# IR_Interface_Board.net
KiCad netlist of a schematic drawn in EAGLE
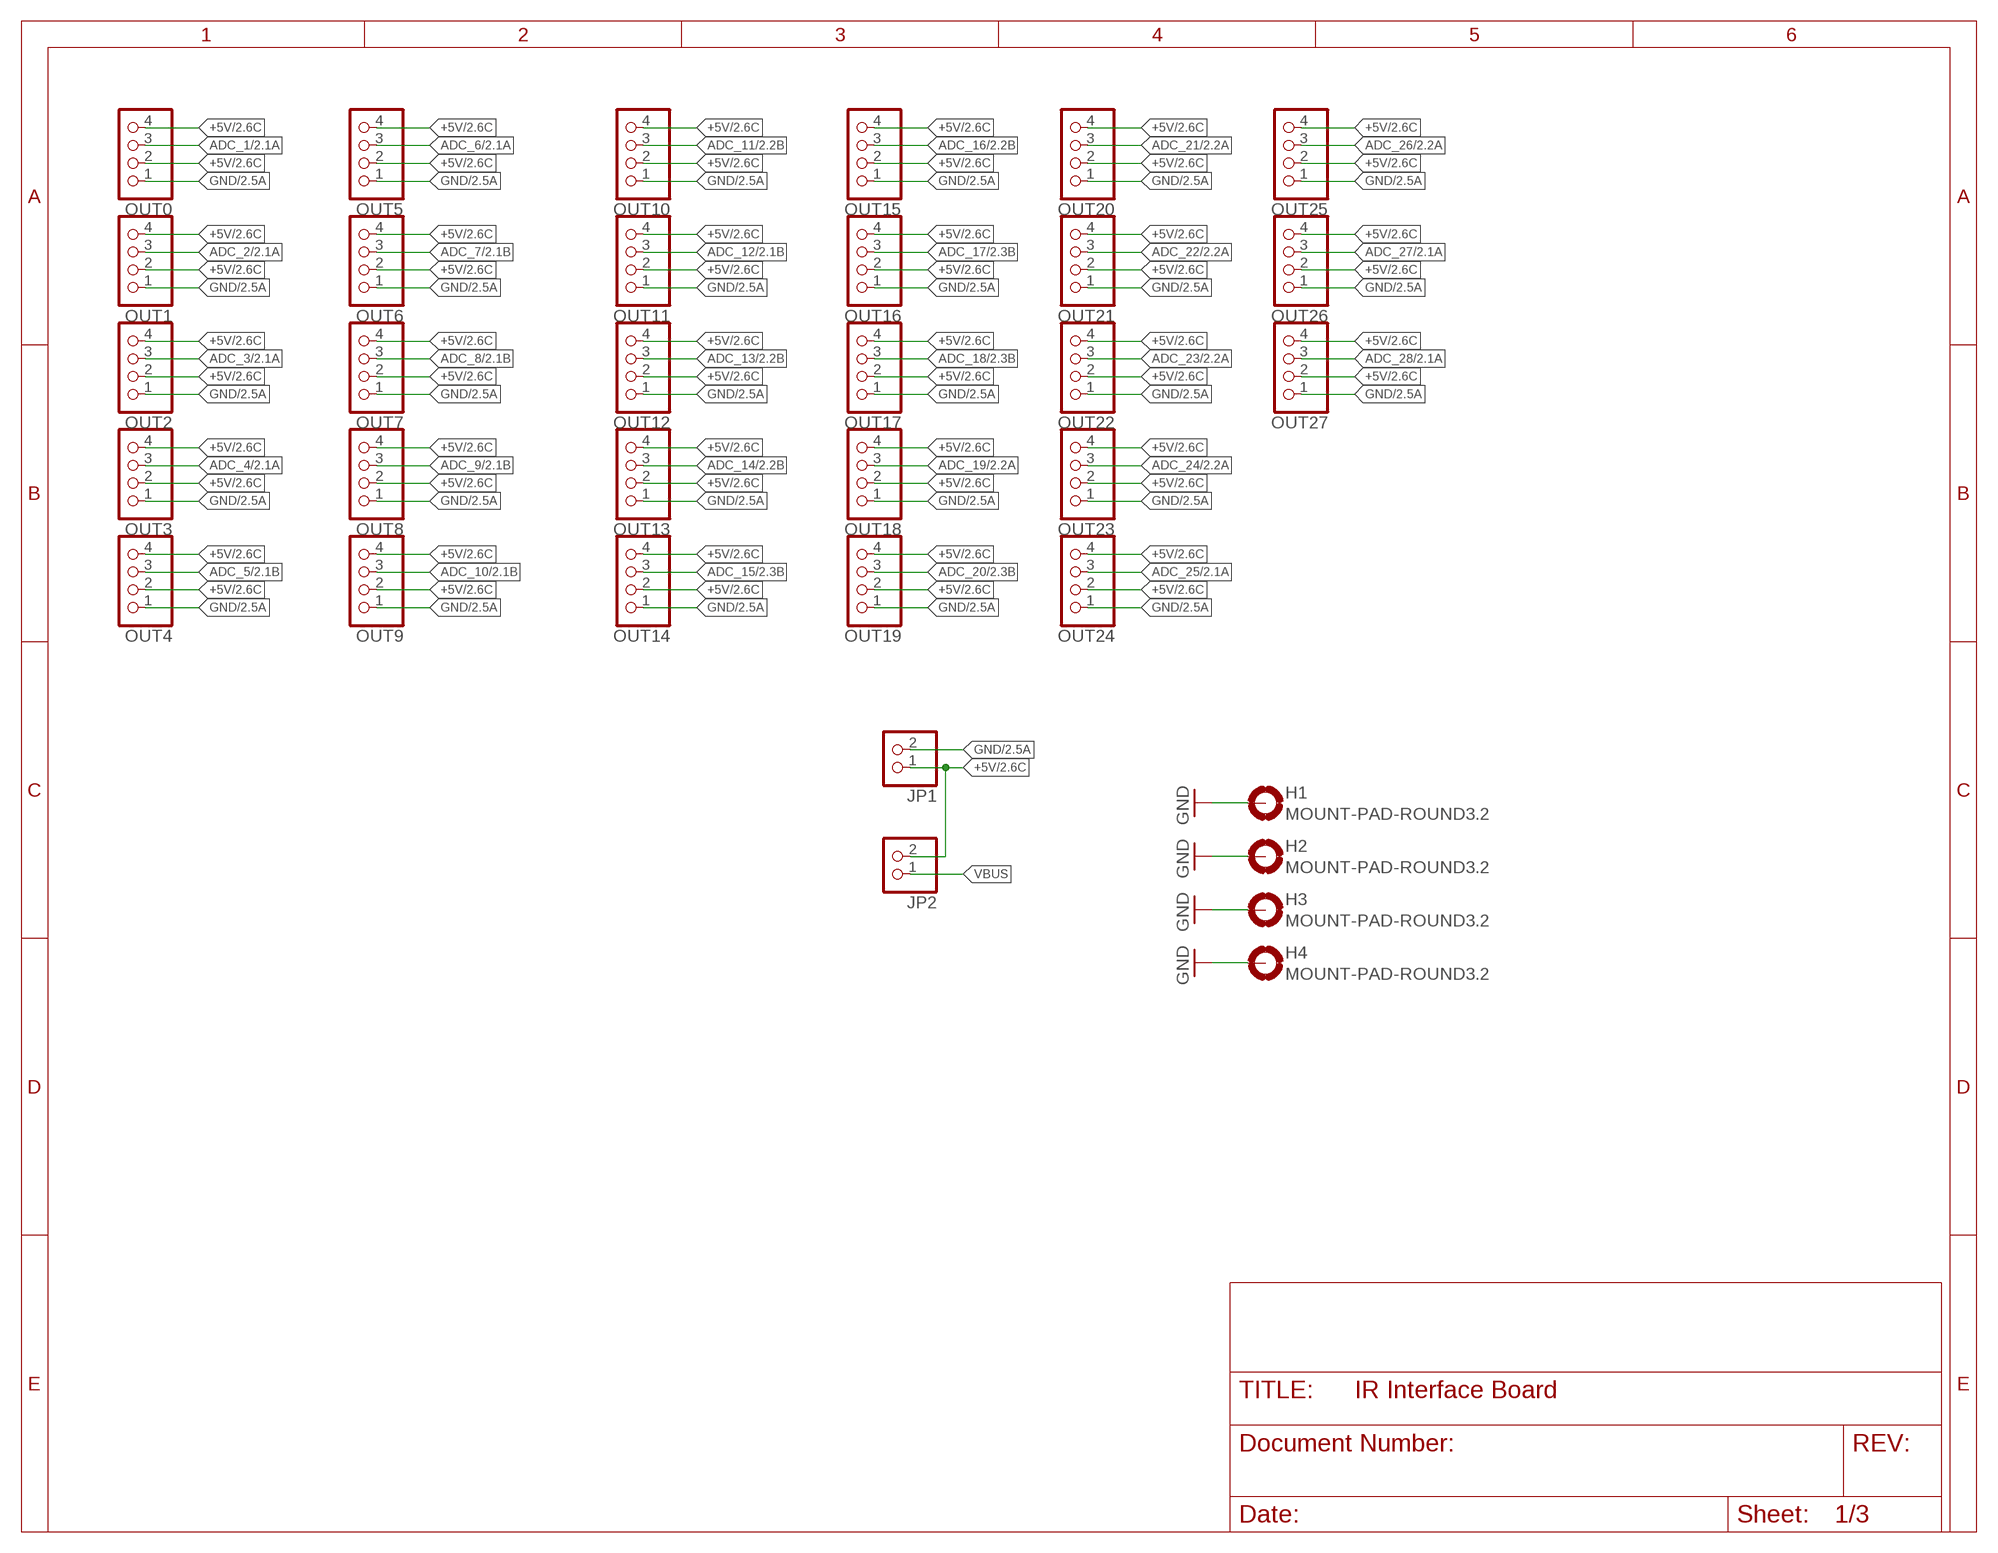
[diagram p0: schematic, sheet 1]
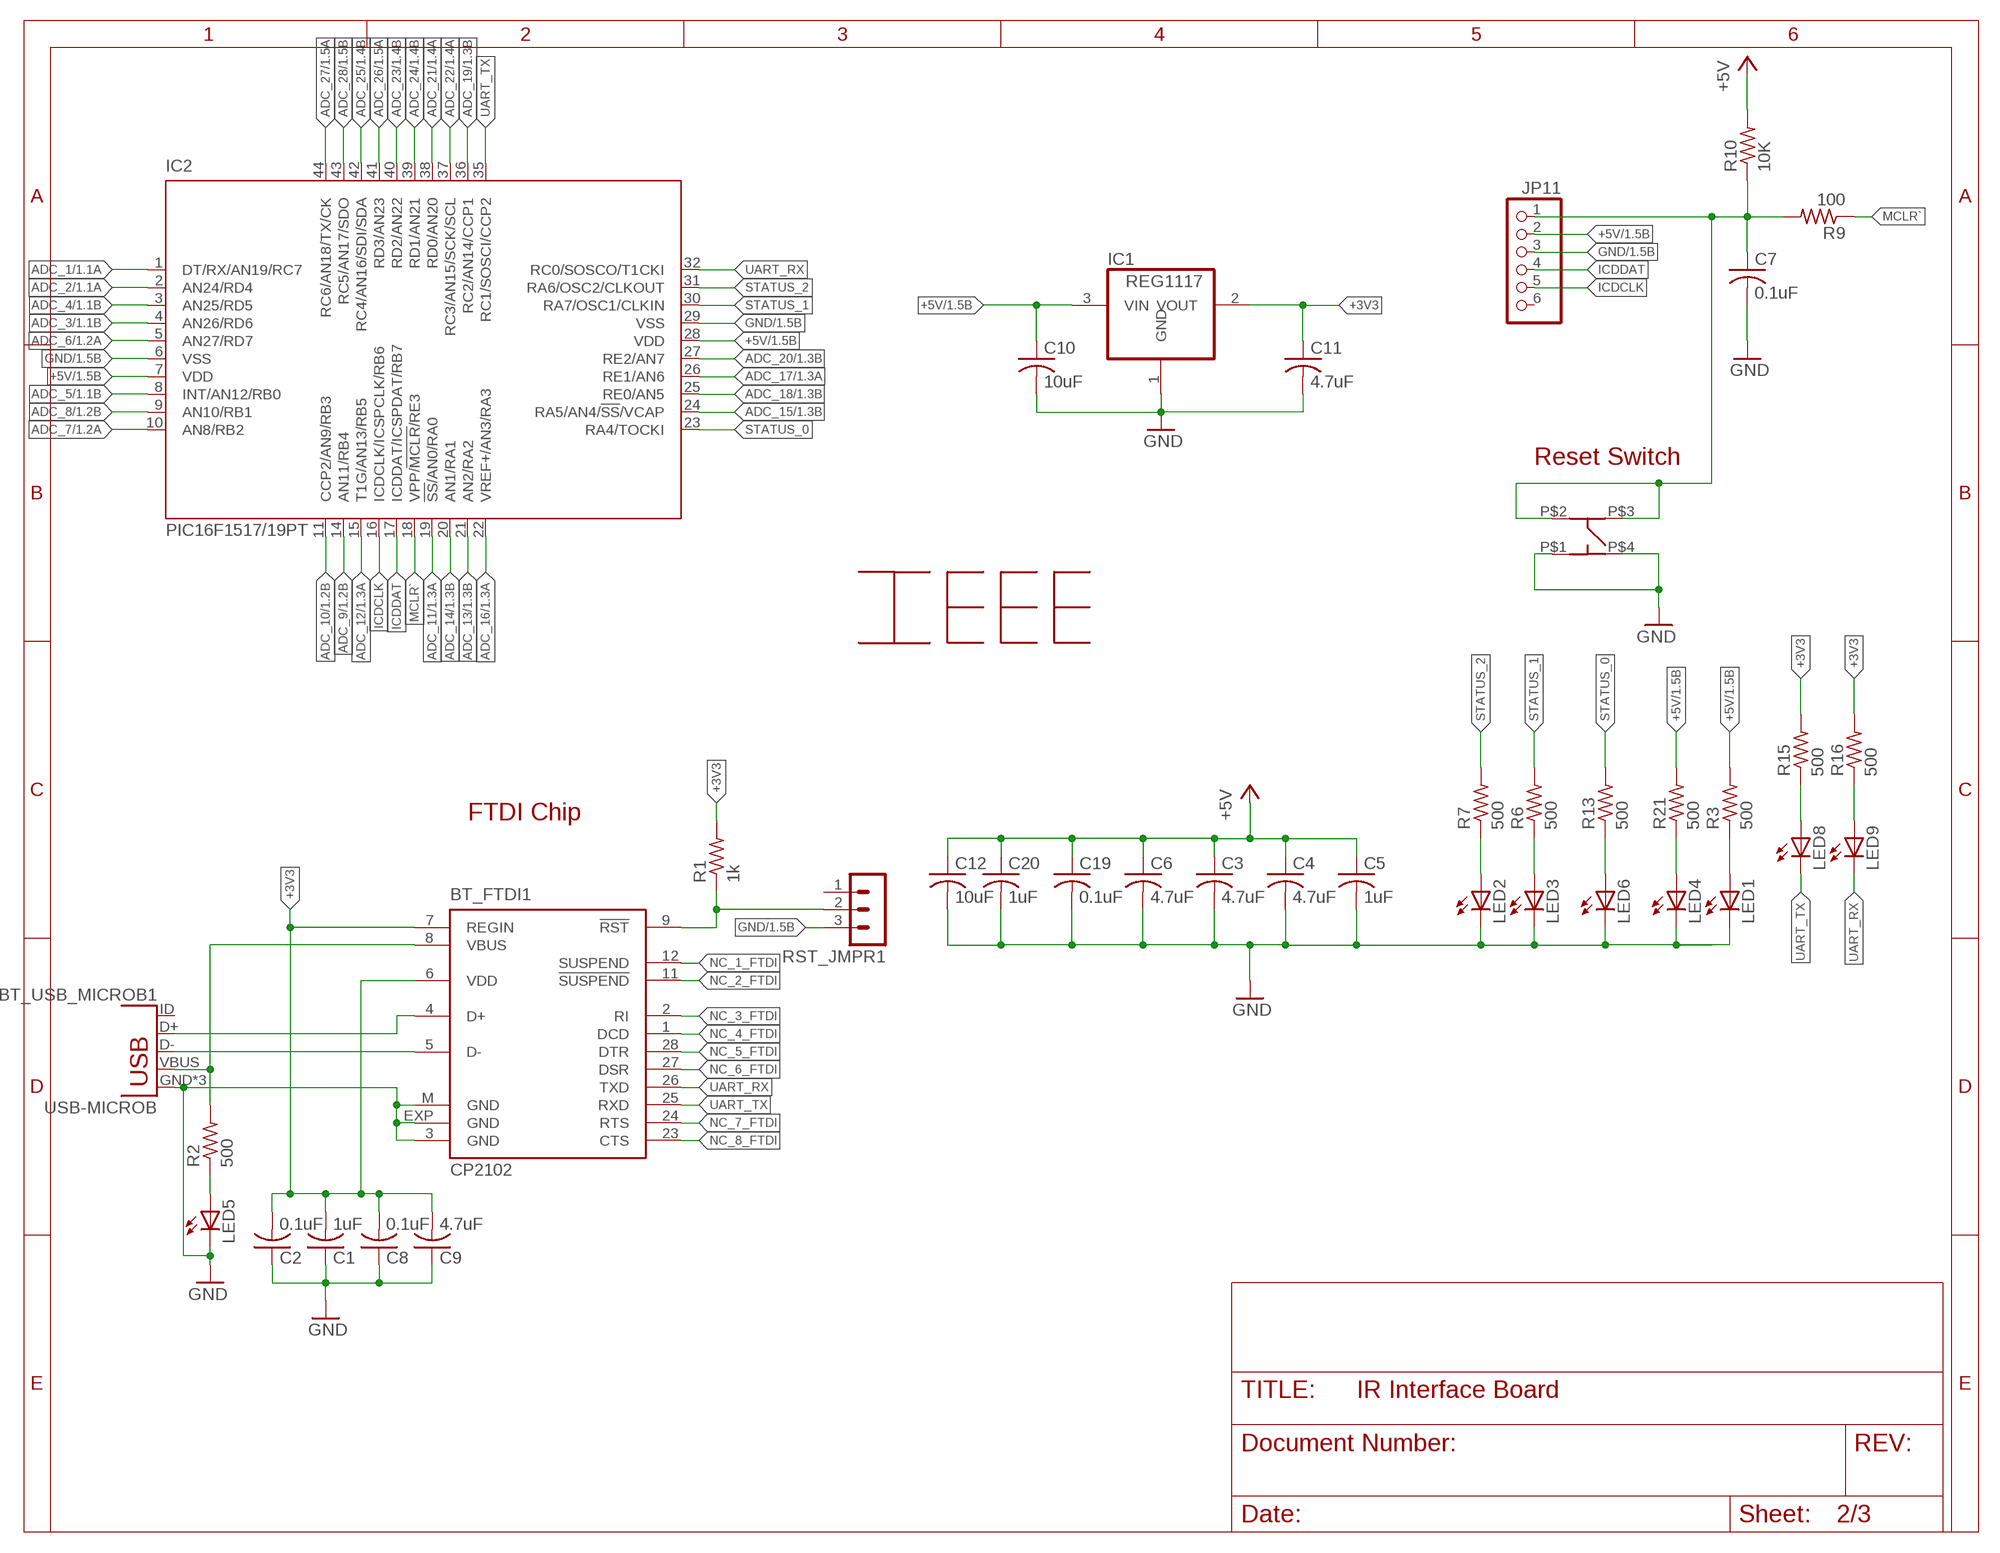
[diagram p1: schematic, sheet 2]
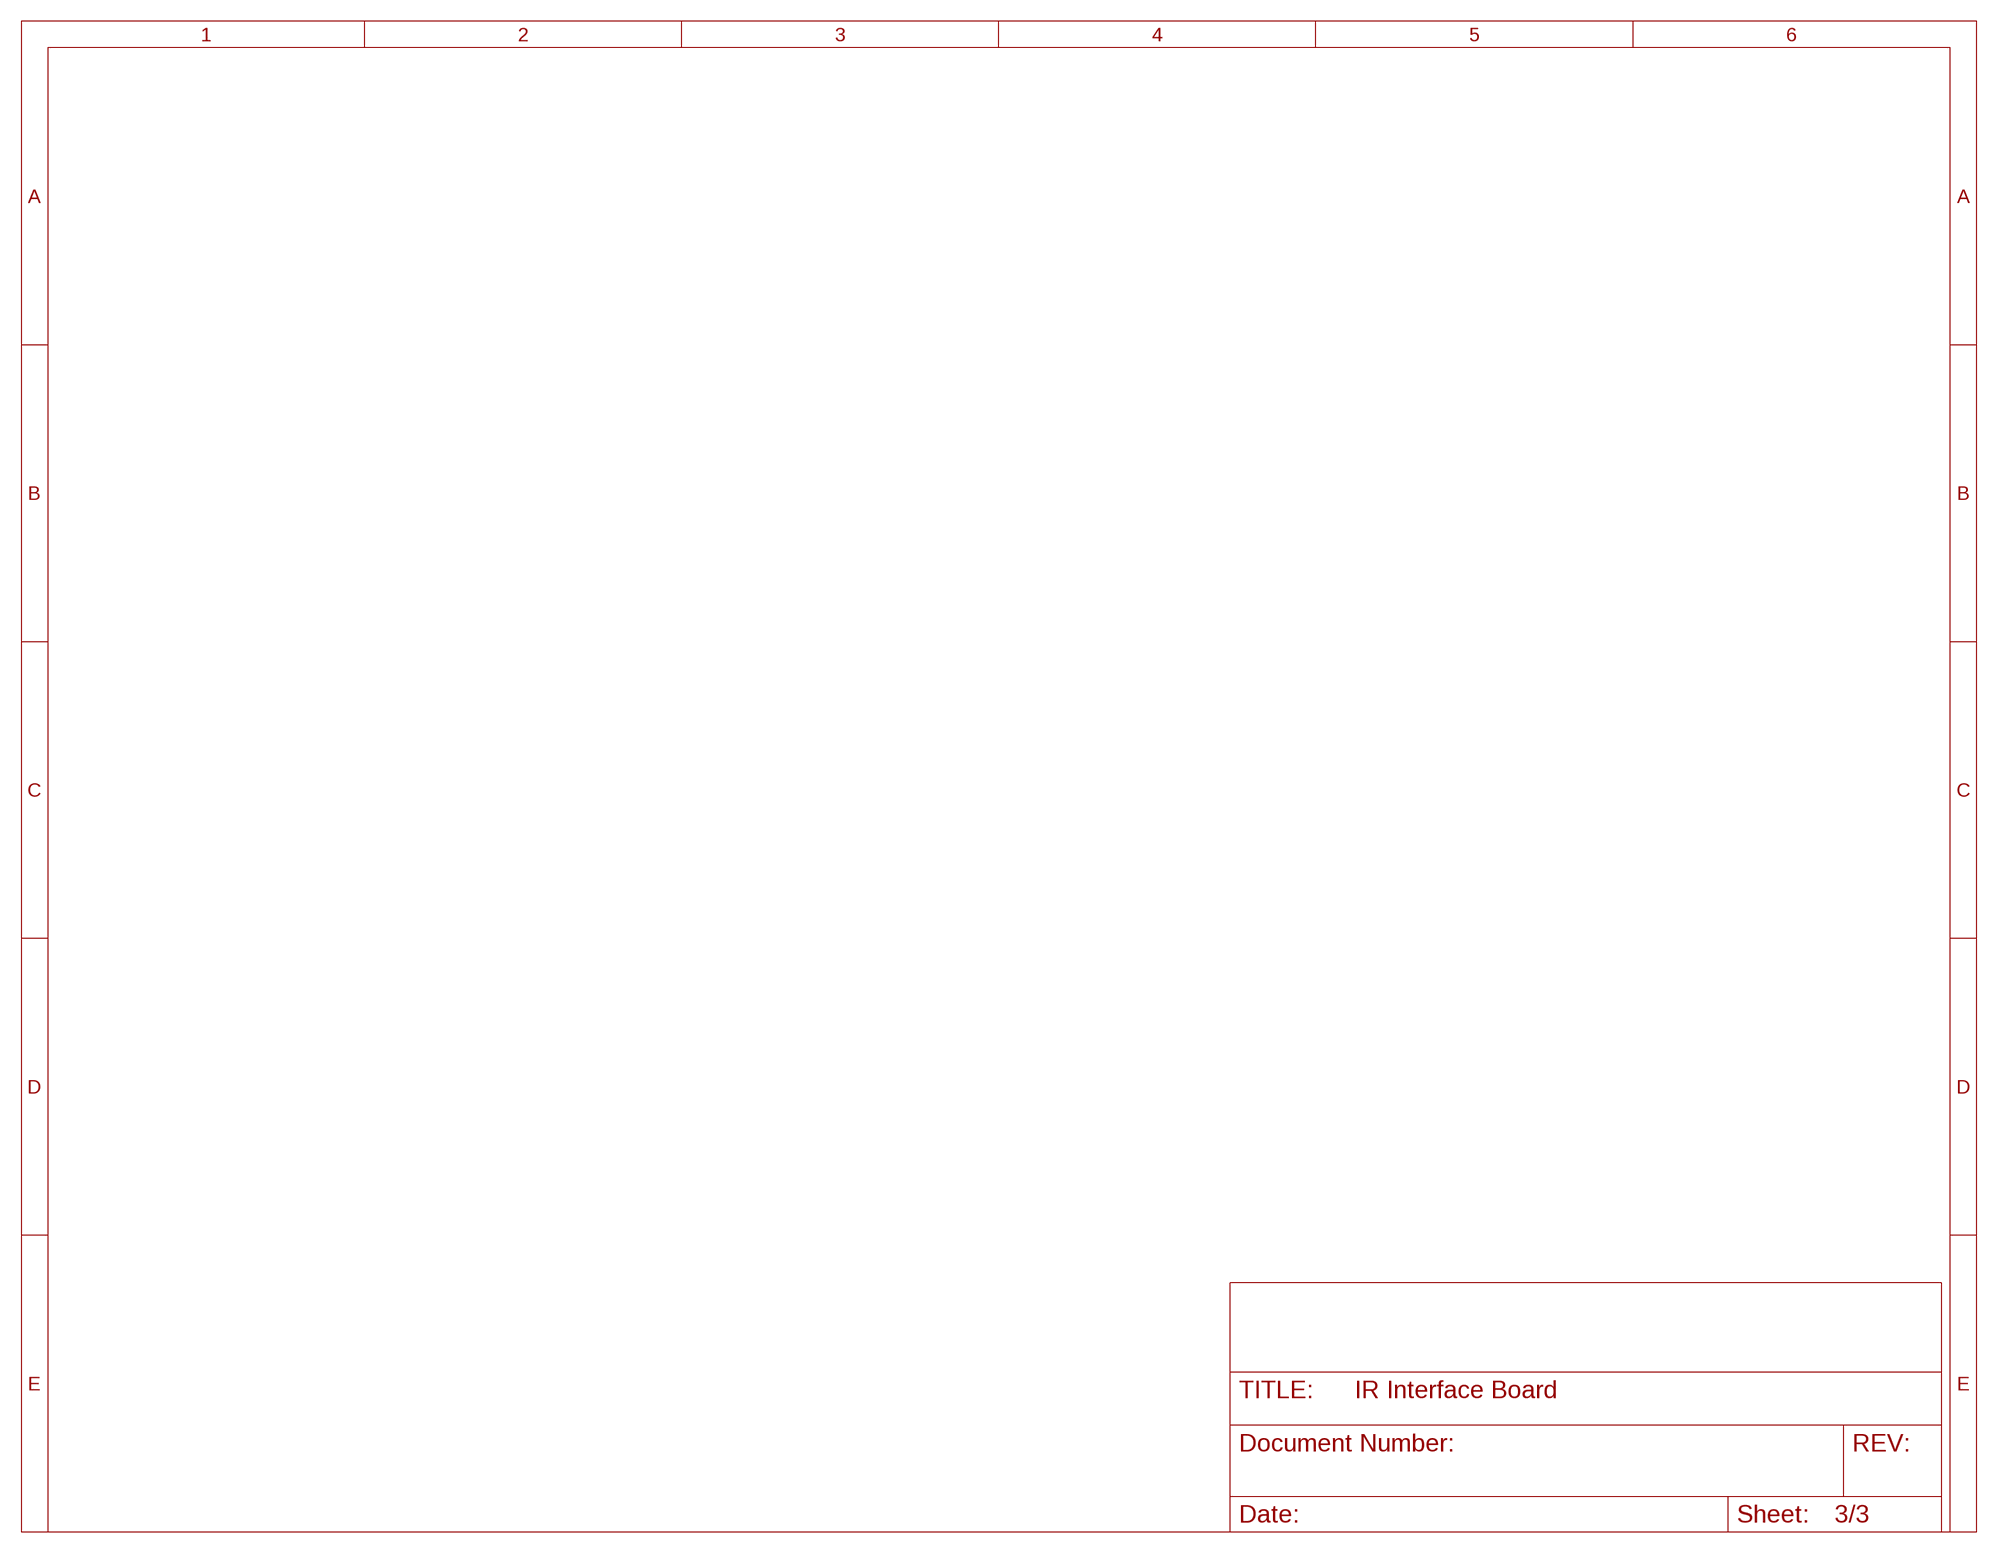
[diagram p2: schematic, sheet 3]

(export (version "E")
  (design (tool "Eeschema 10.0.6"))
  (components
    (comp (ref "BT_FTDI1")
      (value "CP2102")
      (footprint "eagle-import:MLP28")
      (fields (field (name "MF") "FARNELL") (field (name "MPN") "CP2102-GM"))
      (libsource (lib "eagle-import") (part "CP2102"))
    )
    (comp (ref "BT_USB_MICROB1")
      (value "USB-MICROB")
      (footprint "eagle-import:USB-MICROB")
      (libsource (lib "eagle-import") (part "USB-MICROB"))
    )
    (comp (ref "C1")
      (value "1uF")
      (footprint "eagle-import:C0805")
      (libsource (lib "eagle-import") (part "C-USC0805"))
    )
    (comp (ref "C2")
      (value "0.1uF")
      (footprint "eagle-import:C0805")
      (libsource (lib "eagle-import") (part "C-USC0805"))
    )
    (comp (ref "C3")
      (value "4.7uF")
      (footprint "eagle-import:C0805")
      (libsource (lib "eagle-import") (part "C-USC0805"))
    )
    (comp (ref "C4")
      (value "4.7uF")
      (footprint "eagle-import:C0805")
      (libsource (lib "eagle-import") (part "C-USC0805"))
    )
    (comp (ref "C5")
      (value "1uF")
      (footprint "eagle-import:C0805")
      (libsource (lib "eagle-import") (part "C-USC0805"))
    )
    (comp (ref "C6")
      (value "4.7uF")
      (footprint "eagle-import:C0805")
      (libsource (lib "eagle-import") (part "C-USC0805"))
    )
    (comp (ref "C7")
      (value "0.1uF")
      (footprint "eagle-import:C0805")
      (libsource (lib "eagle-import") (part "C-USC0805"))
    )
    (comp (ref "C8")
      (value "0.1uF")
      (footprint "eagle-import:C0805")
      (libsource (lib "eagle-import") (part "C-USC0805"))
    )
    (comp (ref "C9")
      (value "4.7uF")
      (footprint "eagle-import:C0805")
      (libsource (lib "eagle-import") (part "C-USC0805"))
    )
    (comp (ref "C10")
      (value "10uF")
      (footprint "eagle-import:C0805")
      (libsource (lib "eagle-import") (part "C-USC0805"))
    )
    (comp (ref "C11")
      (value "4.7uF")
      (footprint "eagle-import:C0805")
      (libsource (lib "eagle-import") (part "C-USC0805"))
    )
    (comp (ref "C12")
      (value "10uF")
      (footprint "eagle-import:C0805")
      (libsource (lib "eagle-import") (part "C-USC0805"))
    )
    (comp (ref "C19")
      (value "0.1uF")
      (footprint "eagle-import:C0805")
      (libsource (lib "eagle-import") (part "C-USC0805"))
    )
    (comp (ref "C20")
      (value "1uF")
      (footprint "eagle-import:C0805")
      (libsource (lib "eagle-import") (part "C-USC0805"))
    )
    (comp (ref "IC1")
      (value "REG1117")
      (footprint "eagle-import:SOT223")
      (libsource (lib "eagle-import") (part "REG1117"))
    )
    (comp (ref "IC2")
      (value "PIC16F1517/19PT")
      (footprint "eagle-import:TQFP44")
      (libsource (lib "eagle-import") (part "PIC16F1517/19PT"))
    )
    (comp (ref "JP11")
      (value "PINHD-1X6/90")
      (footprint "eagle-import:1X06_90")
      (libsource (lib "eagle-import") (part "PINHD-1X6/90"))
    )
    (comp (ref "LED1")
      (value "LEDSML0603")
      (footprint "eagle-import:SML0603")
      (libsource (lib "eagle-import") (part "LEDSML0603"))
    )
    (comp (ref "LED2")
      (value "LEDSML0603")
      (footprint "eagle-import:SML0603")
      (libsource (lib "eagle-import") (part "LEDSML0603"))
    )
    (comp (ref "LED3")
      (value "LEDSML0603")
      (footprint "eagle-import:SML0603")
      (libsource (lib "eagle-import") (part "LEDSML0603"))
    )
    (comp (ref "LED4")
      (value "LEDSML0603")
      (footprint "eagle-import:SML0603")
      (libsource (lib "eagle-import") (part "LEDSML0603"))
    )
    (comp (ref "LED5")
      (value "LEDSML0603")
      (footprint "eagle-import:SML0603")
      (libsource (lib "eagle-import") (part "LEDSML0603"))
    )
    (comp (ref "LED6")
      (value "LEDSML0603")
      (footprint "eagle-import:SML0603")
      (libsource (lib "eagle-import") (part "LEDSML0603"))
    )
    (comp (ref "LED8")
      (value "LEDSML0603")
      (footprint "eagle-import:SML0603")
      (libsource (lib "eagle-import") (part "LEDSML0603"))
    )
    (comp (ref "LED9")
      (value "LEDSML0603")
      (footprint "eagle-import:SML0603")
      (libsource (lib "eagle-import") (part "LEDSML0603"))
    )
    (comp (ref "R1")
      (value "1k")
      (footprint "eagle-import:R0805")
      (libsource (lib "eagle-import") (part "resistor_R-US_R0805"))
    )
    (comp (ref "R2")
      (value "500")
      (footprint "eagle-import:R0805")
      (libsource (lib "eagle-import") (part "R-US_R0805"))
    )
    (comp (ref "R3")
      (value "500")
      (footprint "eagle-import:R0805")
      (libsource (lib "eagle-import") (part "R-US_R0805"))
    )
    (comp (ref "R6")
      (value "500")
      (footprint "eagle-import:R0805")
      (libsource (lib "eagle-import") (part "R-US_R0805"))
    )
    (comp (ref "R7")
      (value "500")
      (footprint "eagle-import:R0805")
      (libsource (lib "eagle-import") (part "R-US_R0805"))
    )
    (comp (ref "R9")
      (value "100")
      (footprint "eagle-import:R0805")
      (libsource (lib "eagle-import") (part "R-US_R0805"))
    )
    (comp (ref "R10")
      (value "10K")
      (footprint "eagle-import:R0805")
      (libsource (lib "eagle-import") (part "R-US_R0805"))
    )
    (comp (ref "R13")
      (value "500")
      (footprint "eagle-import:R0805")
      (libsource (lib "eagle-import") (part "R-US_R0805"))
    )
    (comp (ref "R15")
      (value "500")
      (footprint "eagle-import:R0805")
      (libsource (lib "eagle-import") (part "R-US_R0805"))
    )
    (comp (ref "R16")
      (value "500")
      (footprint "eagle-import:R0805")
      (libsource (lib "eagle-import") (part "R-US_R0805"))
    )
    (comp (ref "R21")
      (value "500")
      (footprint "eagle-import:R0805")
      (libsource (lib "eagle-import") (part "R-US_R0805"))
    )
    (comp (ref "RST_JMPR1")
      (value "MA03-1")
      (footprint "eagle-import:MA03-1")
      (libsource (lib "eagle-import") (part "MA03-1"))
    )
    (comp (ref "TOUCH_RESET")
      (value "RESET")
      (footprint "eagle-import:MC32882_FINAL")
      (libsource (lib "eagle-import") (part "MC32882_SW"))
    )
    (comp (ref "U$1")
      (value "LOGO")
      (footprint "eagle-import:IEEE-LOGO")
      (libsource (lib "eagle-import") (part "LOGO"))
    )
    (comp (ref "H1")
      (value "MOUNT-PAD-ROUND3.2")
      (footprint "eagle-import:3,2-PAD")
      (libsource (lib "eagle-import") (part "MOUNT-PAD-ROUND3.2"))
    )
    (comp (ref "H2")
      (value "MOUNT-PAD-ROUND3.2")
      (footprint "eagle-import:3,2-PAD")
      (libsource (lib "eagle-import") (part "MOUNT-PAD-ROUND3.2"))
    )
    (comp (ref "H3")
      (value "MOUNT-PAD-ROUND3.2")
      (footprint "eagle-import:3,2-PAD")
      (libsource (lib "eagle-import") (part "MOUNT-PAD-ROUND3.2"))
    )
    (comp (ref "H4")
      (value "MOUNT-PAD-ROUND3.2")
      (footprint "eagle-import:3,2-PAD")
      (libsource (lib "eagle-import") (part "MOUNT-PAD-ROUND3.2"))
    )
    (comp (ref "JP1")
      (value "PINHD-1X2")
      (footprint "eagle-import:1X02")
      (libsource (lib "eagle-import") (part "PINHD-1X2"))
    )
    (comp (ref "JP2")
      (value "PINHD-1X2")
      (footprint "eagle-import:1X02")
      (libsource (lib "eagle-import") (part "PINHD-1X2"))
    )
    (comp (ref "OUT0")
      (value "PINHD-1X4")
      (footprint "eagle-import:1X04")
      (libsource (lib "eagle-import") (part "PINHD-1X4"))
    )
    (comp (ref "OUT1")
      (value "PINHD-1X4")
      (footprint "eagle-import:1X04")
      (libsource (lib "eagle-import") (part "PINHD-1X4"))
    )
    (comp (ref "OUT2")
      (value "PINHD-1X4")
      (footprint "eagle-import:1X04")
      (libsource (lib "eagle-import") (part "PINHD-1X4"))
    )
    (comp (ref "OUT3")
      (value "PINHD-1X4")
      (footprint "eagle-import:1X04")
      (libsource (lib "eagle-import") (part "PINHD-1X4"))
    )
    (comp (ref "OUT4")
      (value "PINHD-1X4")
      (footprint "eagle-import:1X04")
      (libsource (lib "eagle-import") (part "PINHD-1X4"))
    )
    (comp (ref "OUT5")
      (value "PINHD-1X4")
      (footprint "eagle-import:1X04")
      (libsource (lib "eagle-import") (part "PINHD-1X4"))
    )
    (comp (ref "OUT6")
      (value "PINHD-1X4")
      (footprint "eagle-import:1X04")
      (libsource (lib "eagle-import") (part "PINHD-1X4"))
    )
    (comp (ref "OUT7")
      (value "PINHD-1X4")
      (footprint "eagle-import:1X04")
      (libsource (lib "eagle-import") (part "PINHD-1X4"))
    )
    (comp (ref "OUT8")
      (value "PINHD-1X4")
      (footprint "eagle-import:1X04")
      (libsource (lib "eagle-import") (part "PINHD-1X4"))
    )
    (comp (ref "OUT9")
      (value "PINHD-1X4")
      (footprint "eagle-import:1X04")
      (libsource (lib "eagle-import") (part "PINHD-1X4"))
    )
    (comp (ref "OUT10")
      (value "PINHD-1X4")
      (footprint "eagle-import:1X04")
      (libsource (lib "eagle-import") (part "PINHD-1X4"))
    )
    (comp (ref "OUT11")
      (value "PINHD-1X4")
      (footprint "eagle-import:1X04")
      (libsource (lib "eagle-import") (part "PINHD-1X4"))
    )
    (comp (ref "OUT12")
      (value "PINHD-1X4")
      (footprint "eagle-import:1X04")
      (libsource (lib "eagle-import") (part "PINHD-1X4"))
    )
    (comp (ref "OUT13")
      (value "PINHD-1X4")
      (footprint "eagle-import:1X04")
      (libsource (lib "eagle-import") (part "PINHD-1X4"))
    )
    (comp (ref "OUT14")
      (value "PINHD-1X4")
      (footprint "eagle-import:1X04")
      (libsource (lib "eagle-import") (part "PINHD-1X4"))
    )
    (comp (ref "OUT15")
      (value "PINHD-1X4")
      (footprint "eagle-import:1X04")
      (libsource (lib "eagle-import") (part "PINHD-1X4"))
    )
    (comp (ref "OUT16")
      (value "PINHD-1X4")
      (footprint "eagle-import:1X04")
      (libsource (lib "eagle-import") (part "PINHD-1X4"))
    )
    (comp (ref "OUT17")
      (value "PINHD-1X4")
      (footprint "eagle-import:1X04")
      (libsource (lib "eagle-import") (part "PINHD-1X4"))
    )
    (comp (ref "OUT18")
      (value "PINHD-1X4")
      (footprint "eagle-import:1X04")
      (libsource (lib "eagle-import") (part "PINHD-1X4"))
    )
    (comp (ref "OUT19")
      (value "PINHD-1X4")
      (footprint "eagle-import:1X04")
      (libsource (lib "eagle-import") (part "PINHD-1X4"))
    )
    (comp (ref "OUT20")
      (value "PINHD-1X4")
      (footprint "eagle-import:1X04")
      (libsource (lib "eagle-import") (part "PINHD-1X4"))
    )
    (comp (ref "OUT21")
      (value "PINHD-1X4")
      (footprint "eagle-import:1X04")
      (libsource (lib "eagle-import") (part "PINHD-1X4"))
    )
    (comp (ref "OUT22")
      (value "PINHD-1X4")
      (footprint "eagle-import:1X04")
      (libsource (lib "eagle-import") (part "PINHD-1X4"))
    )
    (comp (ref "OUT23")
      (value "PINHD-1X4")
      (footprint "eagle-import:1X04")
      (libsource (lib "eagle-import") (part "PINHD-1X4"))
    )
    (comp (ref "OUT24")
      (value "PINHD-1X4")
      (footprint "eagle-import:1X04")
      (libsource (lib "eagle-import") (part "PINHD-1X4"))
    )
    (comp (ref "OUT25")
      (value "PINHD-1X4")
      (footprint "eagle-import:1X04")
      (libsource (lib "eagle-import") (part "PINHD-1X4"))
    )
    (comp (ref "OUT26")
      (value "PINHD-1X4")
      (footprint "eagle-import:1X04")
      (libsource (lib "eagle-import") (part "PINHD-1X4"))
    )
    (comp (ref "OUT27")
      (value "PINHD-1X4")
      (footprint "eagle-import:1X04")
      (libsource (lib "eagle-import") (part "PINHD-1X4"))
    )
  )
  (nets
    (net (code "1") (name "+3V3") (class "Default")
      (node (ref "BT_FTDI1") (pin "6") (pinfunction "VDD_6") (pintype "power_in"))
      (node (ref "BT_FTDI1") (pin "7") (pinfunction "REGIN_7") (pintype "passive"))
      (node (ref "C1") (pin "2") (pinfunction "2_2") (pintype "passive"))
      (node (ref "C11") (pin "1") (pinfunction "1_1") (pintype "passive"))
      (node (ref "C2") (pin "2") (pinfunction "2_2") (pintype "passive"))
      (node (ref "C8") (pin "2") (pinfunction "2_2") (pintype "passive"))
      (node (ref "C9") (pin "2") (pinfunction "2_2") (pintype "passive"))
      (node (ref "IC1") (pin "2") (pinfunction "VOUT_2") (pintype "output"))
      (node (ref "R1") (pin "2") (pinfunction "2_2") (pintype "passive"))
      (node (ref "R15") (pin "2") (pinfunction "2_2") (pintype "passive"))
      (node (ref "R16") (pin "2") (pinfunction "2_2") (pintype "passive"))
    )
    (net (code "2") (name "+5V") (class "Default")
      (node (ref "C10") (pin "1") (pinfunction "1_1") (pintype "passive"))
      (node (ref "C12") (pin "1") (pinfunction "1_1") (pintype "passive"))
      (node (ref "C19") (pin "1") (pinfunction "1_1") (pintype "passive"))
      (node (ref "C20") (pin "1") (pinfunction "1_1") (pintype "passive"))
      (node (ref "C3") (pin "1") (pinfunction "1_1") (pintype "passive"))
      (node (ref "C4") (pin "1") (pinfunction "1_1") (pintype "passive"))
      (node (ref "C5") (pin "1") (pinfunction "1_1") (pintype "passive"))
      (node (ref "C6") (pin "1") (pinfunction "1_1") (pintype "passive"))
      (node (ref "IC1") (pin "3") (pinfunction "VIN_3") (pintype "input"))
      (node (ref "IC2") (pin "28") (pinfunction "VDD_28") (pintype "power_in"))
      (node (ref "IC2") (pin "7") (pinfunction "VDD_7") (pintype "power_in"))
      (node (ref "JP1") (pin "1") (pinfunction "1_1") (pintype "passive"))
      (node (ref "JP11") (pin "2") (pinfunction "2_2") (pintype "passive"))
      (node (ref "JP2") (pin "2") (pinfunction "2_2") (pintype "passive"))
      (node (ref "OUT0") (pin "2") (pinfunction "2_2") (pintype "passive"))
      (node (ref "OUT0") (pin "4") (pinfunction "4_4") (pintype "passive"))
      (node (ref "OUT1") (pin "2") (pinfunction "2_2") (pintype "passive"))
      (node (ref "OUT1") (pin "4") (pinfunction "4_4") (pintype "passive"))
      (node (ref "OUT10") (pin "2") (pinfunction "2_2") (pintype "passive"))
      (node (ref "OUT10") (pin "4") (pinfunction "4_4") (pintype "passive"))
      (node (ref "OUT11") (pin "2") (pinfunction "2_2") (pintype "passive"))
      (node (ref "OUT11") (pin "4") (pinfunction "4_4") (pintype "passive"))
      (node (ref "OUT12") (pin "2") (pinfunction "2_2") (pintype "passive"))
      (node (ref "OUT12") (pin "4") (pinfunction "4_4") (pintype "passive"))
      (node (ref "OUT13") (pin "2") (pinfunction "2_2") (pintype "passive"))
      (node (ref "OUT13") (pin "4") (pinfunction "4_4") (pintype "passive"))
      (node (ref "OUT14") (pin "2") (pinfunction "2_2") (pintype "passive"))
      (node (ref "OUT14") (pin "4") (pinfunction "4_4") (pintype "passive"))
      (node (ref "OUT15") (pin "2") (pinfunction "2_2") (pintype "passive"))
      (node (ref "OUT15") (pin "4") (pinfunction "4_4") (pintype "passive"))
      (node (ref "OUT16") (pin "2") (pinfunction "2_2") (pintype "passive"))
      (node (ref "OUT16") (pin "4") (pinfunction "4_4") (pintype "passive"))
      (node (ref "OUT17") (pin "2") (pinfunction "2_2") (pintype "passive"))
      (node (ref "OUT17") (pin "4") (pinfunction "4_4") (pintype "passive"))
      (node (ref "OUT18") (pin "2") (pinfunction "2_2") (pintype "passive"))
      (node (ref "OUT18") (pin "4") (pinfunction "4_4") (pintype "passive"))
      (node (ref "OUT19") (pin "2") (pinfunction "2_2") (pintype "passive"))
      (node (ref "OUT19") (pin "4") (pinfunction "4_4") (pintype "passive"))
      (node (ref "OUT2") (pin "2") (pinfunction "2_2") (pintype "passive"))
      (node (ref "OUT2") (pin "4") (pinfunction "4_4") (pintype "passive"))
      (node (ref "OUT20") (pin "2") (pinfunction "2_2") (pintype "passive"))
      (node (ref "OUT20") (pin "4") (pinfunction "4_4") (pintype "passive"))
      (node (ref "OUT21") (pin "2") (pinfunction "2_2") (pintype "passive"))
      (node (ref "OUT21") (pin "4") (pinfunction "4_4") (pintype "passive"))
      (node (ref "OUT22") (pin "2") (pinfunction "2_2") (pintype "passive"))
      (node (ref "OUT22") (pin "4") (pinfunction "4_4") (pintype "passive"))
      (node (ref "OUT23") (pin "2") (pinfunction "2_2") (pintype "passive"))
      (node (ref "OUT23") (pin "4") (pinfunction "4_4") (pintype "passive"))
      (node (ref "OUT24") (pin "2") (pinfunction "2_2") (pintype "passive"))
      (node (ref "OUT24") (pin "4") (pinfunction "4_4") (pintype "passive"))
      (node (ref "OUT25") (pin "2") (pinfunction "2_2") (pintype "passive"))
      (node (ref "OUT25") (pin "4") (pinfunction "4_4") (pintype "passive"))
      (node (ref "OUT26") (pin "2") (pinfunction "2_2") (pintype "passive"))
      (node (ref "OUT26") (pin "4") (pinfunction "4_4") (pintype "passive"))
      (node (ref "OUT27") (pin "2") (pinfunction "2_2") (pintype "passive"))
      (node (ref "OUT27") (pin "4") (pinfunction "4_4") (pintype "passive"))
      (node (ref "OUT3") (pin "2") (pinfunction "2_2") (pintype "passive"))
      (node (ref "OUT3") (pin "4") (pinfunction "4_4") (pintype "passive"))
      (node (ref "OUT4") (pin "2") (pinfunction "2_2") (pintype "passive"))
      (node (ref "OUT4") (pin "4") (pinfunction "4_4") (pintype "passive"))
      (node (ref "OUT5") (pin "2") (pinfunction "2_2") (pintype "passive"))
      (node (ref "OUT5") (pin "4") (pinfunction "4_4") (pintype "passive"))
      (node (ref "OUT6") (pin "2") (pinfunction "2_2") (pintype "passive"))
      (node (ref "OUT6") (pin "4") (pinfunction "4_4") (pintype "passive"))
      (node (ref "OUT7") (pin "2") (pinfunction "2_2") (pintype "passive"))
      (node (ref "OUT7") (pin "4") (pinfunction "4_4") (pintype "passive"))
      (node (ref "OUT8") (pin "2") (pinfunction "2_2") (pintype "passive"))
      (node (ref "OUT8") (pin "4") (pinfunction "4_4") (pintype "passive"))
      (node (ref "OUT9") (pin "2") (pinfunction "2_2") (pintype "passive"))
      (node (ref "OUT9") (pin "4") (pinfunction "4_4") (pintype "passive"))
      (node (ref "R10") (pin "2") (pinfunction "2_2") (pintype "passive"))
      (node (ref "R21") (pin "2") (pinfunction "2_2") (pintype "passive"))
      (node (ref "R3") (pin "2") (pinfunction "2_2") (pintype "passive"))
    )
    (net (code "3") (name "ADC_1") (class "Default")
      (node (ref "IC2") (pin "1") (pinfunction "DT/RX/AN19/RC7_1") (pintype "bidirectional"))
      (node (ref "OUT0") (pin "3") (pinfunction "3_3") (pintype "passive"))
    )
    (net (code "4") (name "ADC_2") (class "Default")
      (node (ref "IC2") (pin "2") (pinfunction "AN24/RD4_2") (pintype "bidirectional"))
      (node (ref "OUT1") (pin "3") (pinfunction "3_3") (pintype "passive"))
    )
    (net (code "5") (name "ADC_3") (class "Default")
      (node (ref "IC2") (pin "4") (pinfunction "AN26/RD6_4") (pintype "bidirectional"))
      (node (ref "OUT2") (pin "3") (pinfunction "3_3") (pintype "passive"))
    )
    (net (code "6") (name "ADC_4") (class "Default")
      (node (ref "IC2") (pin "3") (pinfunction "AN25/RD5_3") (pintype "bidirectional"))
      (node (ref "OUT3") (pin "3") (pinfunction "3_3") (pintype "passive"))
    )
    (net (code "7") (name "ADC_5") (class "Default")
      (node (ref "IC2") (pin "8") (pinfunction "INT/AN12/RB0_8") (pintype "bidirectional"))
      (node (ref "OUT4") (pin "3") (pinfunction "3_3") (pintype "passive"))
    )
    (net (code "8") (name "ADC_6") (class "Default")
      (node (ref "IC2") (pin "5") (pinfunction "AN27/RD7_5") (pintype "bidirectional"))
      (node (ref "OUT5") (pin "3") (pinfunction "3_3") (pintype "passive"))
    )
    (net (code "9") (name "ADC_7") (class "Default")
      (node (ref "IC2") (pin "10") (pinfunction "AN8/RB2_10") (pintype "bidirectional"))
      (node (ref "OUT6") (pin "3") (pinfunction "3_3") (pintype "passive"))
    )
    (net (code "10") (name "ADC_8") (class "Default")
      (node (ref "IC2") (pin "9") (pinfunction "AN10/RB1_9") (pintype "bidirectional"))
      (node (ref "OUT7") (pin "3") (pinfunction "3_3") (pintype "passive"))
    )
    (net (code "11") (name "ADC_9") (class "Default")
      (node (ref "IC2") (pin "14") (pinfunction "AN11/RB4_14") (pintype "bidirectional"))
      (node (ref "OUT8") (pin "3") (pinfunction "3_3") (pintype "passive"))
    )
    (net (code "12") (name "ADC_10") (class "Default")
      (node (ref "IC2") (pin "11") (pinfunction "CCP2/AN9/RB3_11") (pintype "bidirectional"))
      (node (ref "OUT9") (pin "3") (pinfunction "3_3") (pintype "passive"))
    )
    (net (code "13") (name "ADC_11") (class "Default")
      (node (ref "IC2") (pin "19") (pinfunction "~{SS}/AN0/RA0_19") (pintype "bidirectional"))
      (node (ref "OUT10") (pin "3") (pinfunction "3_3") (pintype "passive"))
    )
    (net (code "14") (name "ADC_12") (class "Default")
      (node (ref "IC2") (pin "15") (pinfunction "T1G/AN13/RB5_15") (pintype "bidirectional"))
      (node (ref "OUT11") (pin "3") (pinfunction "3_3") (pintype "passive"))
    )
    (net (code "15") (name "ADC_13") (class "Default")
      (node (ref "IC2") (pin "21") (pinfunction "AN2/RA2_21") (pintype "bidirectional"))
      (node (ref "OUT12") (pin "3") (pinfunction "3_3") (pintype "passive"))
    )
    (net (code "16") (name "ADC_14") (class "Default")
      (node (ref "IC2") (pin "20") (pinfunction "AN1/RA1_20") (pintype "bidirectional"))
      (node (ref "OUT13") (pin "3") (pinfunction "3_3") (pintype "passive"))
    )
    (net (code "17") (name "ADC_15") (class "Default")
      (node (ref "IC2") (pin "24") (pinfunction "RA5/AN4/~{SS}/VCAP_24") (pintype "bidirectional"))
      (node (ref "OUT14") (pin "3") (pinfunction "3_3") (pintype "passive"))
    )
    (net (code "18") (name "ADC_16") (class "Default")
      (node (ref "IC2") (pin "22") (pinfunction "VREF+/AN3/RA3_22") (pintype "bidirectional"))
      (node (ref "OUT15") (pin "3") (pinfunction "3_3") (pintype "passive"))
    )
    (net (code "19") (name "ADC_17") (class "Default")
      (node (ref "IC2") (pin "26") (pinfunction "RE1/AN6_26") (pintype "bidirectional"))
      (node (ref "OUT16") (pin "3") (pinfunction "3_3") (pintype "passive"))
    )
    (net (code "20") (name "ADC_18") (class "Default")
      (node (ref "IC2") (pin "25") (pinfunction "RE0/AN5_25") (pintype "bidirectional"))
      (node (ref "OUT17") (pin "3") (pinfunction "3_3") (pintype "passive"))
    )
    (net (code "21") (name "ADC_19") (class "Default")
      (node (ref "IC2") (pin "36") (pinfunction "RC2/AN14/CCP1_36") (pintype "bidirectional"))
      (node (ref "OUT18") (pin "3") (pinfunction "3_3") (pintype "passive"))
    )
    (net (code "22") (name "ADC_20") (class "Default")
      (node (ref "IC2") (pin "27") (pinfunction "RE2/AN7_27") (pintype "bidirectional"))
      (node (ref "OUT19") (pin "3") (pinfunction "3_3") (pintype "passive"))
    )
    (net (code "23") (name "ADC_21") (class "Default")
      (node (ref "IC2") (pin "38") (pinfunction "RD0/AN20_38") (pintype "bidirectional"))
      (node (ref "OUT20") (pin "3") (pinfunction "3_3") (pintype "passive"))
    )
    (net (code "24") (name "ADC_22") (class "Default")
      (node (ref "IC2") (pin "37") (pinfunction "RC3/AN15/SCK/SCL_37") (pintype "bidirectional"))
      (node (ref "OUT21") (pin "3") (pinfunction "3_3") (pintype "passive"))
    )
    (net (code "25") (name "ADC_23") (class "Default")
      (node (ref "IC2") (pin "40") (pinfunction "RD2/AN22_40") (pintype "bidirectional"))
      (node (ref "OUT22") (pin "3") (pinfunction "3_3") (pintype "passive"))
    )
    (net (code "26") (name "ADC_24") (class "Default")
      (node (ref "IC2") (pin "39") (pinfunction "RD1/AN21_39") (pintype "bidirectional"))
      (node (ref "OUT23") (pin "3") (pinfunction "3_3") (pintype "passive"))
    )
    (net (code "27") (name "ADC_25") (class "Default")
      (node (ref "IC2") (pin "42") (pinfunction "RC4/AN16/SDI/SDA_42") (pintype "bidirectional"))
      (node (ref "OUT24") (pin "3") (pinfunction "3_3") (pintype "passive"))
    )
    (net (code "28") (name "ADC_26") (class "Default")
      (node (ref "IC2") (pin "41") (pinfunction "RD3/AN23_41") (pintype "bidirectional"))
      (node (ref "OUT25") (pin "3") (pinfunction "3_3") (pintype "passive"))
    )
    (net (code "29") (name "ADC_27") (class "Default")
      (node (ref "IC2") (pin "44") (pinfunction "RC6/AN18/TX/CK_44") (pintype "bidirectional"))
      (node (ref "OUT26") (pin "3") (pinfunction "3_3") (pintype "passive"))
    )
    (net (code "30") (name "ADC_28") (class "Default")
      (node (ref "IC2") (pin "43") (pinfunction "RC5/AN17/SDO_43") (pintype "bidirectional"))
      (node (ref "OUT27") (pin "3") (pinfunction "3_3") (pintype "passive"))
    )
    (net (code "31") (name "GND") (class "Default")
      (node (ref "BT_FTDI1") (pin "3") (pinfunction "GND_3") (pintype "power_in"))
      (node (ref "BT_FTDI1") (pin "EXP") (pinfunction "GND_EXP") (pintype "power_in"))
      (node (ref "BT_FTDI1") (pin "M") (pinfunction "GND_M") (pintype "power_in"))
      (node (ref "BT_USB_MICROB1") (pin "GND") (pinfunction "GND_GND") (pintype "bidirectional"))
      (node (ref "BT_USB_MICROB1") (pin "MT1") (pinfunction "GND_MT1") (pintype "bidirectional"))
      (node (ref "BT_USB_MICROB1") (pin "MT2") (pinfunction "GND_MT2") (pintype "bidirectional"))
      (node (ref "C1") (pin "1") (pinfunction "1_1") (pintype "passive"))
      (node (ref "C10") (pin "2") (pinfunction "2_2") (pintype "passive"))
      (node (ref "C11") (pin "2") (pinfunction "2_2") (pintype "passive"))
      (node (ref "C12") (pin "2") (pinfunction "2_2") (pintype "passive"))
      (node (ref "C19") (pin "2") (pinfunction "2_2") (pintype "passive"))
      (node (ref "C2") (pin "1") (pinfunction "1_1") (pintype "passive"))
      (node (ref "C20") (pin "2") (pinfunction "2_2") (pintype "passive"))
      (node (ref "C3") (pin "2") (pinfunction "2_2") (pintype "passive"))
      (node (ref "C4") (pin "2") (pinfunction "2_2") (pintype "passive"))
      (node (ref "C5") (pin "2") (pinfunction "2_2") (pintype "passive"))
      (node (ref "C6") (pin "2") (pinfunction "2_2") (pintype "passive"))
      (node (ref "C7") (pin "2") (pinfunction "2_2") (pintype "passive"))
      (node (ref "C8") (pin "1") (pinfunction "1_1") (pintype "passive"))
      (node (ref "C9") (pin "1") (pinfunction "1_1") (pintype "passive"))
      (node (ref "H1") (pin "B3,2") (pinfunction "MOUNT_B3,2") (pintype "passive"))
      (node (ref "H2") (pin "B3,2") (pinfunction "MOUNT_B3,2") (pintype "passive"))
      (node (ref "H3") (pin "B3,2") (pinfunction "MOUNT_B3,2") (pintype "passive"))
      (node (ref "H4") (pin "B3,2") (pinfunction "MOUNT_B3,2") (pintype "passive"))
      (node (ref "IC1") (pin "1") (pinfunction "GND_1") (pintype "power_in"))
      (node (ref "IC2") (pin "29") (pinfunction "VSS_29") (pintype "power_in"))
      (node (ref "IC2") (pin "6") (pinfunction "VSS_6") (pintype "power_in"))
      (node (ref "JP1") (pin "2") (pinfunction "2_2") (pintype "passive"))
      (node (ref "JP11") (pin "3") (pinfunction "3_3") (pintype "passive"))
      (node (ref "LED1") (pin "C") (pinfunction "C_C") (pintype "passive"))
      (node (ref "LED2") (pin "C") (pinfunction "C_C") (pintype "passive"))
      (node (ref "LED3") (pin "C") (pinfunction "C_C") (pintype "passive"))
      (node (ref "LED4") (pin "C") (pinfunction "C_C") (pintype "passive"))
      (node (ref "LED5") (pin "C") (pinfunction "C_C") (pintype "passive"))
      (node (ref "LED6") (pin "C") (pinfunction "C_C") (pintype "passive"))
      (node (ref "OUT0") (pin "1") (pinfunction "1_1") (pintype "passive"))
      (node (ref "OUT1") (pin "1") (pinfunction "1_1") (pintype "passive"))
      (node (ref "OUT10") (pin "1") (pinfunction "1_1") (pintype "passive"))
      (node (ref "OUT11") (pin "1") (pinfunction "1_1") (pintype "passive"))
      (node (ref "OUT12") (pin "1") (pinfunction "1_1") (pintype "passive"))
      (node (ref "OUT13") (pin "1") (pinfunction "1_1") (pintype "passive"))
      (node (ref "OUT14") (pin "1") (pinfunction "1_1") (pintype "passive"))
      (node (ref "OUT15") (pin "1") (pinfunction "1_1") (pintype "passive"))
      (node (ref "OUT16") (pin "1") (pinfunction "1_1") (pintype "passive"))
      (node (ref "OUT17") (pin "1") (pinfunction "1_1") (pintype "passive"))
      (node (ref "OUT18") (pin "1") (pinfunction "1_1") (pintype "passive"))
      (node (ref "OUT19") (pin "1") (pinfunction "1_1") (pintype "passive"))
      (node (ref "OUT2") (pin "1") (pinfunction "1_1") (pintype "passive"))
      (node (ref "OUT20") (pin "1") (pinfunction "1_1") (pintype "passive"))
      (node (ref "OUT21") (pin "1") (pinfunction "1_1") (pintype "passive"))
      (node (ref "OUT22") (pin "1") (pinfunction "1_1") (pintype "passive"))
      (node (ref "OUT23") (pin "1") (pinfunction "1_1") (pintype "passive"))
      (node (ref "OUT24") (pin "1") (pinfunction "1_1") (pintype "passive"))
      (node (ref "OUT25") (pin "1") (pinfunction "1_1") (pintype "passive"))
      (node (ref "OUT26") (pin "1") (pinfunction "1_1") (pintype "passive"))
      (node (ref "OUT27") (pin "1") (pinfunction "1_1") (pintype "passive"))
      (node (ref "OUT3") (pin "1") (pinfunction "1_1") (pintype "passive"))
      (node (ref "OUT4") (pin "1") (pinfunction "1_1") (pintype "passive"))
      (node (ref "OUT5") (pin "1") (pinfunction "1_1") (pintype "passive"))
      (node (ref "OUT6") (pin "1") (pinfunction "1_1") (pintype "passive"))
      (node (ref "OUT7") (pin "1") (pinfunction "1_1") (pintype "passive"))
      (node (ref "OUT8") (pin "1") (pinfunction "1_1") (pintype "passive"))
      (node (ref "OUT9") (pin "1") (pinfunction "1_1") (pintype "passive"))
      (node (ref "RST_JMPR1") (pin "3") (pinfunction "3_3") (pintype "passive"))
      (node (ref "TOUCH_RESET") (pin "P$1") (pinfunction "P1_P$1") (pintype "bidirectional"))
      (node (ref "TOUCH_RESET") (pin "P$4") (pinfunction "P4_P$4") (pintype "bidirectional"))
    )
    (net (code "32") (name "ICDCLK") (class "Default")
      (node (ref "IC2") (pin "16") (pinfunction "ICDCLK/ICSPCLK/RB6_16") (pintype "bidirectional"))
      (node (ref "JP11") (pin "5") (pinfunction "5_5") (pintype "passive"))
    )
    (net (code "33") (name "ICDDAT") (class "Default")
      (node (ref "IC2") (pin "17") (pinfunction "ICDDAT/ICSPDAT/RB7_17") (pintype "bidirectional"))
      (node (ref "JP11") (pin "4") (pinfunction "4_4") (pintype "passive"))
    )
    (net (code "34") (name "MCLR`") (class "Default")
      (node (ref "IC2") (pin "18") (pinfunction "VPP/~{MCLR}/RE3_18") (pintype "input"))
      (node (ref "R9") (pin "1") (pinfunction "1_1") (pintype "passive"))
    )
    (net (code "35") (name "NC_1_FTDI") (class "Default")
      (node (ref "BT_FTDI1") (pin "12") (pinfunction "SUSPEND_12") (pintype "output"))
    )
    (net (code "36") (name "NC_2_FTDI") (class "Default")
      (node (ref "BT_FTDI1") (pin "11") (pinfunction "~{SUSPEND}_11") (pintype "output"))
    )
    (net (code "37") (name "NC_3_FTDI") (class "Default")
      (node (ref "BT_FTDI1") (pin "2") (pinfunction "RI_2") (pintype "input"))
    )
    (net (code "38") (name "NC_4_FTDI") (class "Default")
      (node (ref "BT_FTDI1") (pin "1") (pinfunction "DCD_1") (pintype "input"))
    )
    (net (code "39") (name "NC_5_FTDI") (class "Default")
      (node (ref "BT_FTDI1") (pin "28") (pinfunction "DTR_28") (pintype "output"))
    )
    (net (code "40") (name "NC_6_FTDI") (class "Default")
      (node (ref "BT_FTDI1") (pin "27") (pinfunction "DSR_27") (pintype "input"))
    )
    (net (code "41") (name "NC_7_FTDI") (class "Default")
      (node (ref "BT_FTDI1") (pin "24") (pinfunction "RTS_24") (pintype "output"))
    )
    (net (code "42") (name "NC_8_FTDI") (class "Default")
      (node (ref "BT_FTDI1") (pin "23") (pinfunction "CTS_23") (pintype "input"))
    )
    (net (code "43") (name "Net-(BT_FTDI1-D+)") (class "Default")
      (node (ref "BT_FTDI1") (pin "4") (pinfunction "D+_4") (pintype "bidirectional"))
      (node (ref "BT_USB_MICROB1") (pin "D+") (pinfunction "D+_D+") (pintype "bidirectional"))
    )
    (net (code "44") (name "Net-(BT_FTDI1-D-)") (class "Default")
      (node (ref "BT_FTDI1") (pin "5") (pinfunction "D-_5") (pintype "bidirectional"))
      (node (ref "BT_USB_MICROB1") (pin "D-") (pinfunction "D-_D-") (pintype "bidirectional"))
    )
    (net (code "45") (name "Net-(BT_FTDI1-~{RST})") (class "Default")
      (node (ref "BT_FTDI1") (pin "9") (pinfunction "~{RST}_9") (pintype "bidirectional"))
      (node (ref "R1") (pin "1") (pinfunction "1_1") (pintype "passive"))
      (node (ref "RST_JMPR1") (pin "2") (pinfunction "2_2") (pintype "passive"))
    )
    (net (code "46") (name "Net-(LED1-PadA)") (class "Default")
      (node (ref "LED1") (pin "A") (pinfunction "A_A") (pintype "passive"))
      (node (ref "R3") (pin "1") (pinfunction "1_1") (pintype "passive"))
    )
    (net (code "47") (name "Net-(LED2-PadA)") (class "Default")
      (node (ref "LED2") (pin "A") (pinfunction "A_A") (pintype "passive"))
      (node (ref "R7") (pin "1") (pinfunction "1_1") (pintype "passive"))
    )
    (net (code "48") (name "Net-(LED3-PadA)") (class "Default")
      (node (ref "LED3") (pin "A") (pinfunction "A_A") (pintype "passive"))
      (node (ref "R6") (pin "1") (pinfunction "1_1") (pintype "passive"))
    )
    (net (code "49") (name "Net-(LED4-PadA)") (class "Default")
      (node (ref "LED4") (pin "A") (pinfunction "A_A") (pintype "passive"))
      (node (ref "R21") (pin "1") (pinfunction "1_1") (pintype "passive"))
    )
    (net (code "50") (name "Net-(LED5-PadA)") (class "Default")
      (node (ref "LED5") (pin "A") (pinfunction "A_A") (pintype "passive"))
      (node (ref "R2") (pin "1") (pinfunction "1_1") (pintype "passive"))
    )
    (net (code "51") (name "Net-(LED6-PadA)") (class "Default")
      (node (ref "LED6") (pin "A") (pinfunction "A_A") (pintype "passive"))
      (node (ref "R13") (pin "1") (pinfunction "1_1") (pintype "passive"))
    )
    (net (code "52") (name "Net-(LED8-PadA)") (class "Default")
      (node (ref "LED8") (pin "A") (pinfunction "A_A") (pintype "passive"))
      (node (ref "R15") (pin "1") (pinfunction "1_1") (pintype "passive"))
    )
    (net (code "53") (name "Net-(LED9-PadA)") (class "Default")
      (node (ref "LED9") (pin "A") (pinfunction "A_A") (pintype "passive"))
      (node (ref "R16") (pin "1") (pinfunction "1_1") (pintype "passive"))
    )
    (net (code "54") (name "Net-(TOUCH_RESET-P2)") (class "Default")
      (node (ref "C7") (pin "1") (pinfunction "1_1") (pintype "passive"))
      (node (ref "JP11") (pin "1") (pinfunction "1_1") (pintype "passive"))
      (node (ref "R10") (pin "1") (pinfunction "1_1") (pintype "passive"))
      (node (ref "R9") (pin "2") (pinfunction "2_2") (pintype "passive"))
      (node (ref "TOUCH_RESET") (pin "P$2") (pinfunction "P2_P$2") (pintype "bidirectional"))
      (node (ref "TOUCH_RESET") (pin "P$3") (pinfunction "P3_P$3") (pintype "bidirectional"))
    )
    (net (code "55") (name "STATUS_0") (class "Default")
      (node (ref "IC2") (pin "23") (pinfunction "RA4/TOCKI_23") (pintype "bidirectional"))
      (node (ref "R13") (pin "2") (pinfunction "2_2") (pintype "passive"))
    )
    (net (code "56") (name "STATUS_1") (class "Default")
      (node (ref "IC2") (pin "30") (pinfunction "RA7/OSC1/CLKIN_30") (pintype "bidirectional"))
      (node (ref "R6") (pin "2") (pinfunction "2_2") (pintype "passive"))
    )
    (net (code "57") (name "STATUS_2") (class "Default")
      (node (ref "IC2") (pin "31") (pinfunction "RA6/OSC2/CLKOUT_31") (pintype "bidirectional"))
      (node (ref "R7") (pin "2") (pinfunction "2_2") (pintype "passive"))
    )
    (net (code "58") (name "UART_RX") (class "Default")
      (node (ref "BT_FTDI1") (pin "26") (pinfunction "TXD_26") (pintype "output"))
      (node (ref "IC2") (pin "32") (pinfunction "RC0/SOSCO/T1CKI_32") (pintype "bidirectional"))
      (node (ref "LED9") (pin "C") (pinfunction "C_C") (pintype "passive"))
    )
    (net (code "59") (name "UART_TX") (class "Default")
      (node (ref "BT_FTDI1") (pin "25") (pinfunction "RXD_25") (pintype "input"))
      (node (ref "IC2") (pin "35") (pinfunction "RC1/SOSCI/CCP2_35") (pintype "bidirectional"))
      (node (ref "LED8") (pin "C") (pinfunction "C_C") (pintype "passive"))
    )
    (net (code "60") (name "VBUS") (class "Default")
      (node (ref "BT_FTDI1") (pin "8") (pinfunction "VBUS_8") (pintype "input"))
      (node (ref "BT_USB_MICROB1") (pin "VBUS") (pinfunction "VBUS_VBUS") (pintype "bidirectional"))
      (node (ref "JP2") (pin "1") (pinfunction "1_1") (pintype "passive"))
      (node (ref "R2") (pin "2") (pinfunction "2_2") (pintype "passive"))
    )
    (net (code "61") (name "unconnected-(BT_USB_MICROB1-PadID)") (class "Default")
      (node (ref "BT_USB_MICROB1") (pin "ID") (pinfunction "ID_ID") (pintype "bidirectional"))
    )
    (net (code "62") (name "unconnected-(JP11-Pad6)") (class "Default")
      (node (ref "JP11") (pin "6") (pinfunction "6_6") (pintype "passive"))
    )
    (net (code "63") (name "unconnected-(RST_JMPR1-Pad1)") (class "Default")
      (node (ref "RST_JMPR1") (pin "1") (pinfunction "1_1") (pintype "passive"))
    )
  )
)
